# NodeReceive.net
KiCad netlist of a schematic drawn in Altium Designer
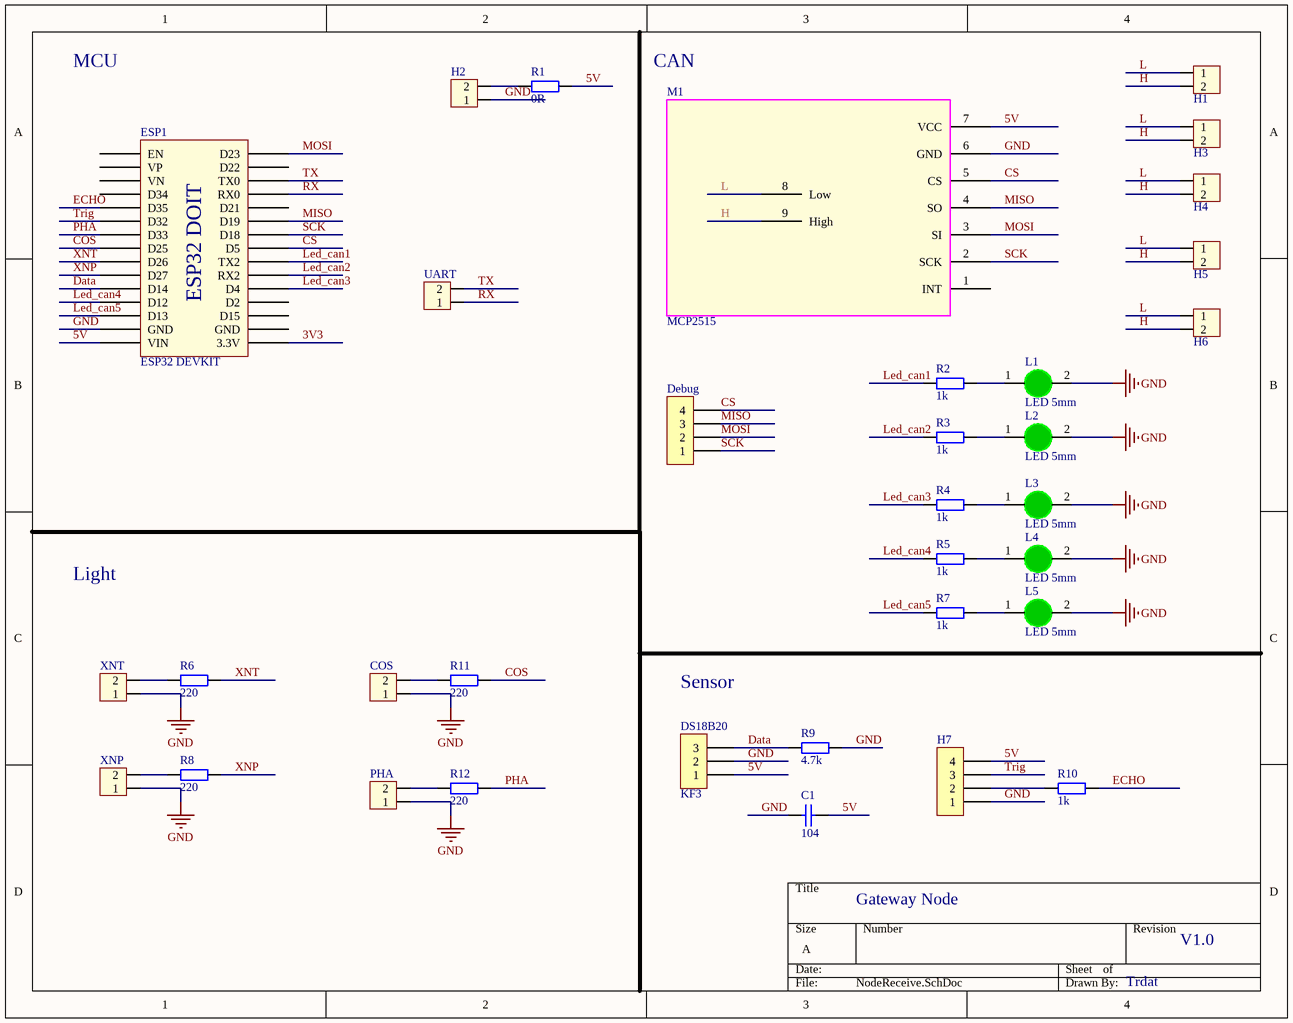
[diagram p0: NodeReceive.SchDoc]

(export (version "E")
  (design (tool "Eeschema 10.0.6"))
  (components
    (comp (ref "C1")
      (value "104")
      (footprint "tu gom")
      (description "Cắm")
      (libsource (lib "Altium_Lib_by_KhueNguyenCreator") (part "Tu gom 104 50V"))
    )
    (comp (ref "COS")
      (value "Header 2P 2.54 Duc Cong")
      (footprint "Header 2P DC 2.54")
      (description "Cắm")
      (libsource (lib "Altium_Lib_by_KhueNguyenCreator") (part "Header 2P 2.54 Duc Cong"))
    )
    (comp (ref "Debug")
      (value "Header 4P 2.54 Duc Cong")
      (footprint "Header 4P DC 2.54")
      (description "Cắm")
      (libsource (lib "My_Component_Library") (part "Header 4P 2.54 Duc Cong"))
    )
    (comp (ref "DS18B20")
      (value "KF3")
      (footprint "KF3-5.08")
      (fields
        (field (name "MANUFACTURER") "Würth Elektronik eiSos GmbH")
        (field (name "PARTNO") "691103110003")
        (field (name "CREATED BY") "Karrer Zheng")
      )
      (libsource (lib "LIBRARY") (part "KF3"))
    )
    (comp (ref "ESP1")
      (value "ESP32 DEVKIT")
      (footprint "ESP32 WROOM 32 KIT")
      (libsource (lib "Altium_Lib_by_KhueNguyenCreator") (part "ESP32 WROOM 32 KIT"))
    )
    (comp (ref "H1")
      (value "Header 2P 2.54 Duc Cong")
      (footprint "Header 2P DC 2.54")
      (description "Cắm")
      (libsource (lib "") (part "Header 2P 2.54 Duc Cong_1"))
    )
    (comp (ref "H2")
      (value "Header 2P 2.54 Duc Cong")
      (footprint "Header 2P DC 2.54")
      (description "Cắm")
      (libsource (lib "Altium_Lib_by_KhueNguyenCreator") (part "Header 2P 2.54 Duc Cong"))
    )
    (comp (ref "H3")
      (value "Header 2P 2.54 Duc Cong")
      (footprint "Header 2P DC 2.54")
      (description "Cắm")
      (libsource (lib "") (part "Header 2P 2.54 Duc Cong_1"))
    )
    (comp (ref "H4")
      (value "Header 2P 2.54 Duc Cong")
      (footprint "Header 2P DC 2.54")
      (description "Cắm")
      (libsource (lib "") (part "Header 2P 2.54 Duc Cong_1"))
    )
    (comp (ref "H5")
      (value "Header 2P 2.54 Duc Cong")
      (footprint "Header 2P DC 2.54")
      (description "Cắm")
      (libsource (lib "") (part "Header 2P 2.54 Duc Cong_1"))
    )
    (comp (ref "H6")
      (value "Header 2P 2.54 Duc Cong")
      (footprint "Header 2P DC 2.54")
      (description "Cắm")
      (libsource (lib "") (part "Header 2P 2.54 Duc Cong_1"))
    )
    (comp (ref "H7")
      (value "Header 4P 2.54 Duc Cong")
      (footprint "Header 4P DC 2.54")
      (description "Cắm")
      (libsource (lib "Altium_Lib_by_KhueNguyenCreator") (part "Header 4P 2.54 Duc Cong"))
    )
    (comp (ref "L1")
      (value "LED 5mm")
      (footprint "LED-5MM-Green")
      (description "Cắm")
      (libsource (lib "Altium_Lib_by_KhueNguyenCreator") (part "LED 5mm Xanh La"))
    )
    (comp (ref "L2")
      (value "LED 5mm")
      (footprint "LED-5MM-Green")
      (description "Cắm")
      (libsource (lib "Altium_Lib_by_KhueNguyenCreator") (part "LED 5mm Xanh La"))
    )
    (comp (ref "L3")
      (value "LED 5mm")
      (footprint "LED-5MM-Green")
      (description "Cắm")
      (libsource (lib "Altium_Lib_by_KhueNguyenCreator") (part "LED 5mm Xanh La"))
    )
    (comp (ref "L4")
      (value "LED 5mm")
      (footprint "LED-5MM-Green")
      (description "Cắm")
      (libsource (lib "Altium_Lib_by_KhueNguyenCreator") (part "LED 5mm Xanh La"))
    )
    (comp (ref "L5")
      (value "LED 5mm")
      (footprint "LED-5MM-Green")
      (description "Cắm")
      (libsource (lib "Altium_Lib_by_KhueNguyenCreator") (part "LED 5mm Xanh La"))
    )
    (comp (ref "M1")
      (value "MCP2515")
      (footprint "MCP2515_MODULE")
      (libsource (lib "My_Component_Library") (part "MCP2515"))
    )
    (comp (ref "PHA")
      (value "Header 2P 2.54 Duc Cong")
      (footprint "Header 2P DC 2.54")
      (description "Cắm")
      (libsource (lib "Altium_Lib_by_KhueNguyenCreator") (part "Header 2P 2.54 Duc Cong"))
    )
    (comp (ref "R1")
      (value "0R")
      (footprint "tro vach 1/4w")
      (description "Cắm")
      (libsource (lib "Altium_Lib_by_KhueNguyenCreator") (part "Tro Vach 1/4W 5% 0.11R"))
    )
    (comp (ref "R2")
      (value "1k")
      (footprint "tro vach 1/4w")
      (description "Cắm")
      (libsource (lib "Altium_Lib_by_KhueNguyenCreator") (part "Tro Vach 1/4W 5% 1k"))
    )
    (comp (ref "R3")
      (value "1k")
      (footprint "tro vach 1/4w")
      (description "Cắm")
      (libsource (lib "Altium_Lib_by_KhueNguyenCreator") (part "Tro Vach 1/4W 5% 1k"))
    )
    (comp (ref "R4")
      (value "1k")
      (footprint "tro vach 1/4w")
      (description "Cắm")
      (libsource (lib "Altium_Lib_by_KhueNguyenCreator") (part "Tro Vach 1/4W 5% 1k"))
    )
    (comp (ref "R5")
      (value "1k")
      (footprint "tro vach 1/4w")
      (description "Cắm")
      (libsource (lib "Altium_Lib_by_KhueNguyenCreator") (part "Tro Vach 1/4W 5% 1k"))
    )
    (comp (ref "R6")
      (value "220")
      (footprint "tro vach 1/4w")
      (description "Cắm")
      (libsource (lib "Altium_Lib_by_KhueNguyenCreator") (part "Tro Vach 1/4W 5% 1k"))
    )
    (comp (ref "R7")
      (value "1k")
      (footprint "tro vach 1/4w")
      (description "Cắm")
      (libsource (lib "Altium_Lib_by_KhueNguyenCreator") (part "Tro Vach 1/4W 5% 1k"))
    )
    (comp (ref "R8")
      (value "220")
      (footprint "tro vach 1/4w")
      (description "Cắm")
      (libsource (lib "Altium_Lib_by_KhueNguyenCreator") (part "Tro Vach 1/4W 5% 1k"))
    )
    (comp (ref "R9")
      (value "4.7k")
      (footprint "tro vach 1/4w")
      (description "Cắm")
      (libsource (lib "Altium_Lib_by_KhueNguyenCreator") (part "Tro Vach 1/4W 5% 4.7k"))
    )
    (comp (ref "R10")
      (value "1k")
      (footprint "tro vach 1/4w")
      (description "Cắm")
      (libsource (lib "Altium_Lib_by_KhueNguyenCreator") (part "Tro Vach 1/4W 5% 1k"))
    )
    (comp (ref "R11")
      (value "220")
      (footprint "tro vach 1/4w")
      (description "Cắm")
      (libsource (lib "Altium_Lib_by_KhueNguyenCreator") (part "Tro Vach 1/4W 5% 1k"))
    )
    (comp (ref "R12")
      (value "220")
      (footprint "tro vach 1/4w")
      (description "Cắm")
      (libsource (lib "Altium_Lib_by_KhueNguyenCreator") (part "Tro Vach 1/4W 5% 1k"))
    )
    (comp (ref "UART")
      (value "Header 2P 2.54 Duc Cong")
      (footprint "Header 2P DC 2.54")
      (description "Cắm")
      (libsource (lib "Altium_Lib_by_KhueNguyenCreator") (part "Header 2P 2.54 Duc Cong"))
    )
    (comp (ref "XNP")
      (value "Header 2P 2.54 Duc Cong")
      (footprint "Header 2P DC 2.54")
      (description "Cắm")
      (libsource (lib "Altium_Lib_by_KhueNguyenCreator") (part "Header 2P 2.54 Duc Cong"))
    )
    (comp (ref "XNT")
      (value "Header 2P 2.54 Duc Cong")
      (footprint "Header 2P DC 2.54")
      (description "Cắm")
      (libsource (lib "Altium_Lib_by_KhueNguyenCreator") (part "Header 2P 2.54 Duc Cong"))
    )
  )
  (nets
    (net (code "1") (name "/3V3") (class "Default")
      (node (ref "ESP1") (pin "16") (pinfunction "3.3V_16") (pintype "passive"))
    )
    (net (code "2") (name "/5V") (class "Default")
      (node (ref "C1") (pin "1") (pinfunction "1_1") (pintype "passive"))
      (node (ref "DS18B20") (pin "1") (pinfunction "1_1") (pintype "passive"))
      (node (ref "ESP1") (pin "15") (pinfunction "VIN_15") (pintype "passive"))
      (node (ref "H7") (pin "4") (pinfunction "4_4") (pintype "passive"))
      (node (ref "M1") (pin "7") (pinfunction "VCC_7") (pintype "power_in"))
      (node (ref "R1") (pin "2") (pinfunction "2_2") (pintype "passive"))
    )
    (net (code "3") (name "/COS") (class "Default")
      (node (ref "ESP1") (pin "8") (pinfunction "D25_8") (pintype "passive"))
      (node (ref "R11") (pin "1") (pinfunction "1_1") (pintype "passive"))
    )
    (net (code "4") (name "/CS") (class "Default")
      (node (ref "Debug") (pin "4") (pinfunction "4_4") (pintype "passive"))
      (node (ref "ESP1") (pin "23") (pinfunction "D5_23") (pintype "passive"))
      (node (ref "M1") (pin "5") (pinfunction "CS_5") (pintype "passive"))
    )
    (net (code "5") (name "/Data") (class "Default")
      (node (ref "DS18B20") (pin "3") (pinfunction "3_3") (pintype "passive"))
      (node (ref "ESP1") (pin "11") (pinfunction "D14_11") (pintype "passive"))
      (node (ref "R9") (pin "1") (pinfunction "1_1") (pintype "passive"))
    )
    (net (code "6") (name "/ECHO") (class "Default")
      (node (ref "ESP1") (pin "5") (pinfunction "D35_5") (pintype "passive"))
      (node (ref "R10") (pin "2") (pinfunction "2_2") (pintype "passive"))
    )
    (net (code "7") (name "/H") (class "Default")
      (node (ref "H1") (pin "2") (pinfunction "2_2") (pintype "passive"))
      (node (ref "H3") (pin "2") (pinfunction "2_2") (pintype "passive"))
      (node (ref "H4") (pin "2") (pinfunction "2_2") (pintype "passive"))
      (node (ref "H5") (pin "2") (pinfunction "2_2") (pintype "passive"))
      (node (ref "H6") (pin "2") (pinfunction "2_2") (pintype "passive"))
      (node (ref "M1") (pin "9") (pinfunction "High_9") (pintype "passive"))
    )
    (net (code "8") (name "/L") (class "Default")
      (node (ref "H1") (pin "1") (pinfunction "1_1") (pintype "passive"))
      (node (ref "H3") (pin "1") (pinfunction "1_1") (pintype "passive"))
      (node (ref "H4") (pin "1") (pinfunction "1_1") (pintype "passive"))
      (node (ref "H5") (pin "1") (pinfunction "1_1") (pintype "passive"))
      (node (ref "H6") (pin "1") (pinfunction "1_1") (pintype "passive"))
      (node (ref "M1") (pin "8") (pinfunction "Low_8") (pintype "passive"))
    )
    (net (code "9") (name "/Led_can1") (class "Default")
      (node (ref "ESP1") (pin "22") (pinfunction "TX2_22") (pintype "passive"))
      (node (ref "R2") (pin "1") (pinfunction "1_1") (pintype "passive"))
    )
    (net (code "10") (name "/Led_can2") (class "Default")
      (node (ref "ESP1") (pin "21") (pinfunction "RX2_21") (pintype "passive"))
      (node (ref "R3") (pin "1") (pinfunction "1_1") (pintype "passive"))
    )
    (net (code "11") (name "/Led_can3") (class "Default")
      (node (ref "ESP1") (pin "20") (pinfunction "D4_20") (pintype "passive"))
      (node (ref "R4") (pin "1") (pinfunction "1_1") (pintype "passive"))
    )
    (net (code "12") (name "/Led_can4") (class "Default")
      (node (ref "ESP1") (pin "12") (pinfunction "D12_12") (pintype "passive"))
      (node (ref "R5") (pin "1") (pinfunction "1_1") (pintype "passive"))
    )
    (net (code "13") (name "/Led_can5") (class "Default")
      (node (ref "ESP1") (pin "13") (pinfunction "D13_13") (pintype "passive"))
      (node (ref "R7") (pin "1") (pinfunction "1_1") (pintype "passive"))
    )
    (net (code "14") (name "/MISO") (class "Default")
      (node (ref "Debug") (pin "3") (pinfunction "3_3") (pintype "passive"))
      (node (ref "ESP1") (pin "25") (pinfunction "D19_25") (pintype "passive"))
      (node (ref "M1") (pin "4") (pinfunction "SO_4") (pintype "passive"))
    )
    (net (code "15") (name "/MOSI") (class "Default")
      (node (ref "Debug") (pin "2") (pinfunction "2_2") (pintype "passive"))
      (node (ref "ESP1") (pin "30") (pinfunction "D23_30") (pintype "passive"))
      (node (ref "M1") (pin "3") (pinfunction "SI_3") (pintype "passive"))
    )
    (net (code "16") (name "/PHA") (class "Default")
      (node (ref "ESP1") (pin "7") (pinfunction "D33_7") (pintype "passive"))
      (node (ref "R12") (pin "1") (pinfunction "1_1") (pintype "passive"))
    )
    (net (code "17") (name "/RX") (class "Default")
      (node (ref "ESP1") (pin "27") (pinfunction "RX0_27") (pintype "passive"))
      (node (ref "UART") (pin "1") (pinfunction "1_1") (pintype "passive"))
    )
    (net (code "18") (name "/SCK") (class "Default")
      (node (ref "Debug") (pin "1") (pinfunction "1_1") (pintype "passive"))
      (node (ref "ESP1") (pin "24") (pinfunction "D18_24") (pintype "passive"))
      (node (ref "M1") (pin "2") (pinfunction "SCK_2") (pintype "passive"))
    )
    (net (code "19") (name "/TX") (class "Default")
      (node (ref "ESP1") (pin "28") (pinfunction "TX0_28") (pintype "passive"))
      (node (ref "UART") (pin "2") (pinfunction "2_2") (pintype "passive"))
    )
    (net (code "20") (name "/Trig") (class "Default")
      (node (ref "ESP1") (pin "6") (pinfunction "D32_6") (pintype "passive"))
      (node (ref "H7") (pin "3") (pinfunction "3_3") (pintype "passive"))
    )
    (net (code "21") (name "/XNP") (class "Default")
      (node (ref "ESP1") (pin "10") (pinfunction "D27_10") (pintype "passive"))
      (node (ref "R8") (pin "1") (pinfunction "1_1") (pintype "passive"))
    )
    (net (code "22") (name "/XNT") (class "Default")
      (node (ref "ESP1") (pin "9") (pinfunction "D26_9") (pintype "passive"))
      (node (ref "R6") (pin "1") (pinfunction "1_1") (pintype "passive"))
    )
    (net (code "23") (name "GND") (class "Default")
      (node (ref "C1") (pin "2") (pinfunction "2_2") (pintype "passive"))
      (node (ref "COS") (pin "1") (pinfunction "1_1") (pintype "passive"))
      (node (ref "DS18B20") (pin "2") (pinfunction "2_2") (pintype "passive"))
      (node (ref "ESP1") (pin "14") (pinfunction "GND_14") (pintype "passive"))
      (node (ref "H2") (pin "1") (pinfunction "1_1") (pintype "passive"))
      (node (ref "H7") (pin "1") (pinfunction "1_1") (pintype "passive"))
      (node (ref "L1") (pin "2") (pinfunction "K_2") (pintype "passive"))
      (node (ref "L2") (pin "2") (pinfunction "K_2") (pintype "passive"))
      (node (ref "L3") (pin "2") (pinfunction "K_2") (pintype "passive"))
      (node (ref "L4") (pin "2") (pinfunction "K_2") (pintype "passive"))
      (node (ref "L5") (pin "2") (pinfunction "K_2") (pintype "passive"))
      (node (ref "M1") (pin "6") (pinfunction "GND_6") (pintype "power_in"))
      (node (ref "PHA") (pin "1") (pinfunction "1_1") (pintype "passive"))
      (node (ref "R9") (pin "2") (pinfunction "2_2") (pintype "passive"))
      (node (ref "XNP") (pin "1") (pinfunction "1_1") (pintype "passive"))
      (node (ref "XNT") (pin "1") (pinfunction "1_1") (pintype "passive"))
    )
    (net (code "24") (name "Net-(COS-Pad2)") (class "Default")
      (node (ref "COS") (pin "2") (pinfunction "2_2") (pintype "passive"))
      (node (ref "R11") (pin "2") (pinfunction "2_2") (pintype "passive"))
    )
    (net (code "25") (name "Net-(H2-Pad2)") (class "Default")
      (node (ref "H2") (pin "2") (pinfunction "2_2") (pintype "passive"))
      (node (ref "R1") (pin "1") (pinfunction "1_1") (pintype "passive"))
    )
    (net (code "26") (name "Net-(H7-Pad2)") (class "Default")
      (node (ref "H7") (pin "2") (pinfunction "2_2") (pintype "passive"))
      (node (ref "R10") (pin "1") (pinfunction "1_1") (pintype "passive"))
    )
    (net (code "27") (name "Net-(L1-A)") (class "Default")
      (node (ref "L1") (pin "1") (pinfunction "A_1") (pintype "passive"))
      (node (ref "R2") (pin "2") (pinfunction "2_2") (pintype "passive"))
    )
    (net (code "28") (name "Net-(L2-A)") (class "Default")
      (node (ref "L2") (pin "1") (pinfunction "A_1") (pintype "passive"))
      (node (ref "R3") (pin "2") (pinfunction "2_2") (pintype "passive"))
    )
    (net (code "29") (name "Net-(L3-A)") (class "Default")
      (node (ref "L3") (pin "1") (pinfunction "A_1") (pintype "passive"))
      (node (ref "R4") (pin "2") (pinfunction "2_2") (pintype "passive"))
    )
    (net (code "30") (name "Net-(L4-A)") (class "Default")
      (node (ref "L4") (pin "1") (pinfunction "A_1") (pintype "passive"))
      (node (ref "R5") (pin "2") (pinfunction "2_2") (pintype "passive"))
    )
    (net (code "31") (name "Net-(L5-A)") (class "Default")
      (node (ref "L5") (pin "1") (pinfunction "A_1") (pintype "passive"))
      (node (ref "R7") (pin "2") (pinfunction "2_2") (pintype "passive"))
    )
    (net (code "32") (name "Net-(PHA-Pad2)") (class "Default")
      (node (ref "PHA") (pin "2") (pinfunction "2_2") (pintype "passive"))
      (node (ref "R12") (pin "2") (pinfunction "2_2") (pintype "passive"))
    )
    (net (code "33") (name "Net-(R6-Pad2)") (class "Default")
      (node (ref "R6") (pin "2") (pinfunction "2_2") (pintype "passive"))
      (node (ref "XNT") (pin "2") (pinfunction "2_2") (pintype "passive"))
    )
    (net (code "34") (name "Net-(R8-Pad2)") (class "Default")
      (node (ref "R8") (pin "2") (pinfunction "2_2") (pintype "passive"))
      (node (ref "XNP") (pin "2") (pinfunction "2_2") (pintype "passive"))
    )
    (net (code "35") (name "unconnected-(ESP1-D2-Pad19)") (class "Default")
      (node (ref "ESP1") (pin "19") (pinfunction "D2_19") (pintype "passive"))
    )
    (net (code "36") (name "unconnected-(ESP1-D15-Pad18)") (class "Default")
      (node (ref "ESP1") (pin "18") (pinfunction "D15_18") (pintype "passive"))
    )
    (net (code "37") (name "unconnected-(ESP1-D21-Pad26)") (class "Default")
      (node (ref "ESP1") (pin "26") (pinfunction "D21_26") (pintype "passive"))
    )
    (net (code "38") (name "unconnected-(ESP1-D22-Pad29)") (class "Default")
      (node (ref "ESP1") (pin "29") (pinfunction "D22_29") (pintype "passive"))
    )
    (net (code "39") (name "unconnected-(ESP1-D34-Pad4)") (class "Default")
      (node (ref "ESP1") (pin "4") (pinfunction "D34_4") (pintype "passive"))
    )
    (net (code "40") (name "unconnected-(ESP1-EN-Pad1)") (class "Default")
      (node (ref "ESP1") (pin "1") (pinfunction "EN_1") (pintype "passive"))
    )
    (net (code "41") (name "unconnected-(ESP1-GND-Pad17)") (class "Default")
      (node (ref "ESP1") (pin "17") (pinfunction "GND_17") (pintype "passive"))
    )
    (net (code "42") (name "unconnected-(ESP1-VN-Pad3)") (class "Default")
      (node (ref "ESP1") (pin "3") (pinfunction "VN_3") (pintype "passive"))
    )
    (net (code "43") (name "unconnected-(ESP1-VP-Pad2)") (class "Default")
      (node (ref "ESP1") (pin "2") (pinfunction "VP_2") (pintype "passive"))
    )
    (net (code "44") (name "unconnected-(M1-INT-Pad1)") (class "Default")
      (node (ref "M1") (pin "1") (pinfunction "INT_1") (pintype "passive"))
    )
  )
)
